# rf_swrmet6.net
KiCad netlist of a schematic drawn in Altium Designer
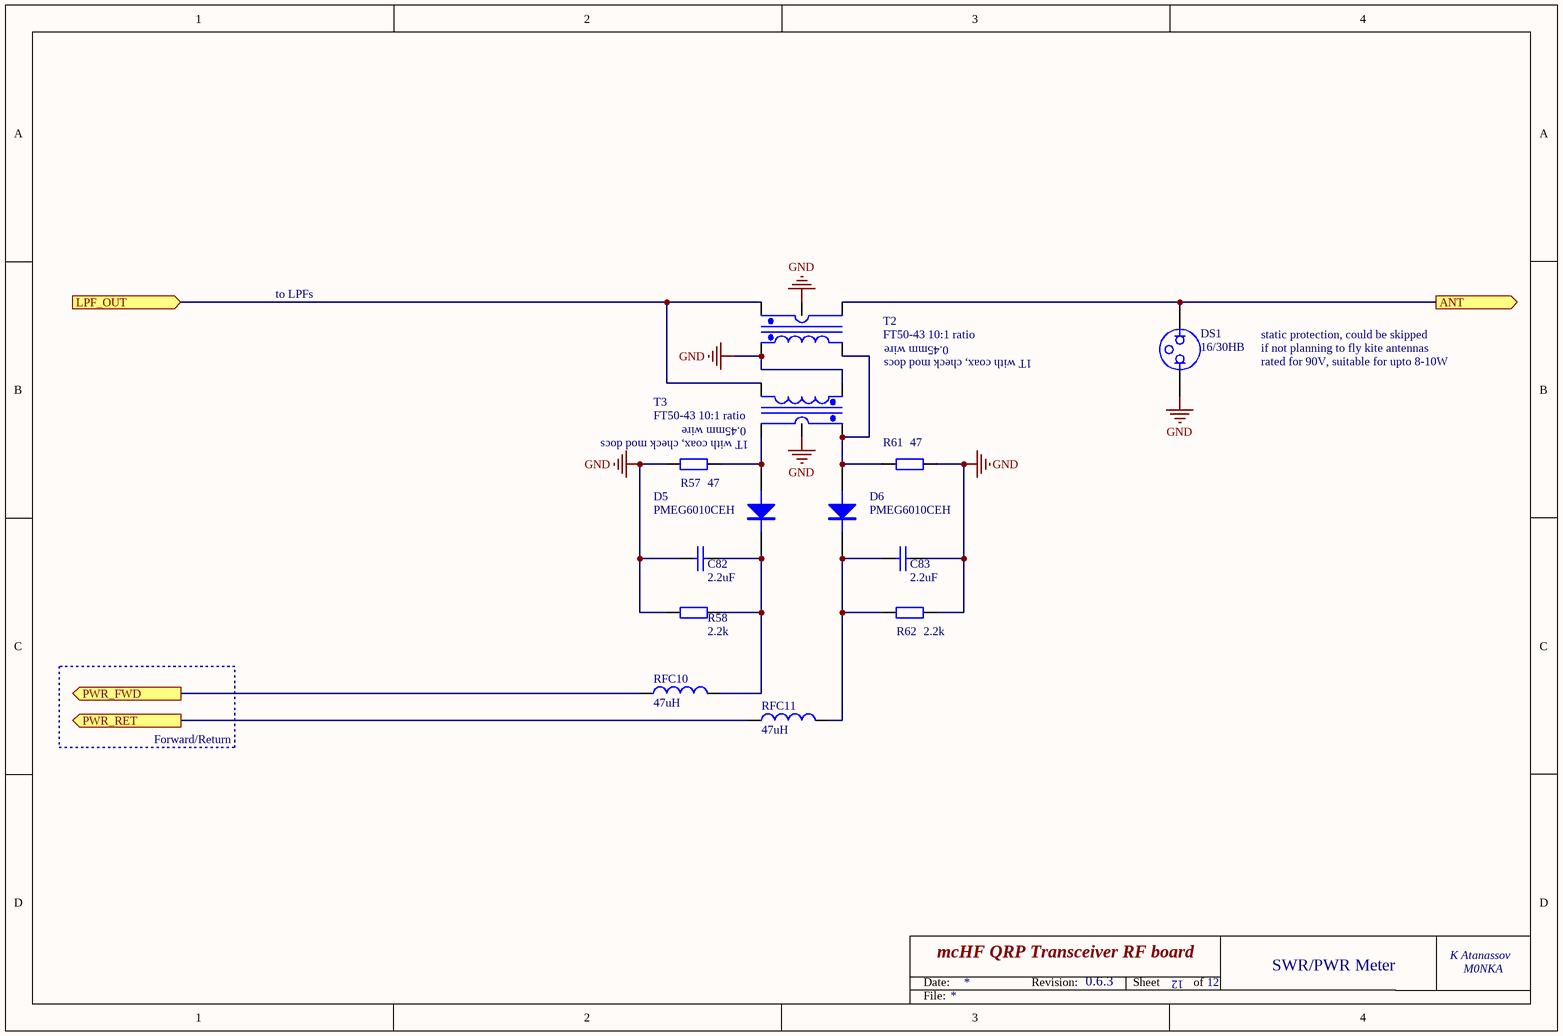
[diagram p0: rf_swrmet6.SchDoc]

(export (version "E")
  (design (tool "Eeschema 10.0.6"))
  (components
    (comp (ref "C82")
      (value "2.2uF")
      (footprint "0805-Pro")
      (description "Capacitor")
      (libsource (lib "mcHF_rf") (part "CAP"))
    )
    (comp (ref "C83")
      (value "2.2uF")
      (footprint "0805-Pro")
      (description "Capacitor")
      (libsource (lib "mcHF_rf") (part "CAP"))
    )
    (comp (ref "D5")
      (value "PMEG6010CEH")
      (footprint "SOD87")
      (description "DIODE, SCHOTTKY, 1A, 60V, SOD-123F")
      (libsource (lib "mcHF_rf") (part "PMEG6010CEH"))
    )
    (comp (ref "D6")
      (value "PMEG6010CEH")
      (footprint "SOD87")
      (description "DIODE, SCHOTTKY, 1A, 60V, SOD-123F")
      (libsource (lib "mcHF_rf") (part "PMEG6010CEH"))
    )
    (comp (ref "DS1")
      (value "16/30HB")
      (footprint "SIP2")
      (description "NEON LAMP, WIRE ENDED, T2")
      (libsource (lib "mcHF_rf") (part "16/30HB"))
    )
    (comp (ref "R57")
      (value "47")
      (footprint "0805-Pro")
      (description "Resistor")
      (libsource (lib "mcHF_rf") (part "RES"))
    )
    (comp (ref "R58")
      (value "2.2k")
      (footprint "0805-Pro")
      (description "Resistor")
      (libsource (lib "mcHF_rf") (part "RES"))
    )
    (comp (ref "R61")
      (value "47")
      (footprint "0805-Pro")
      (description "Resistor")
      (libsource (lib "mcHF_rf") (part "RES"))
    )
    (comp (ref "R62")
      (value "2.2k")
      (footprint "0805-Pro")
      (description "Resistor")
      (libsource (lib "mcHF_rf") (part "RES"))
    )
    (comp (ref "RFC10")
      (value "47uH")
      (footprint "0805-Pro")
      (description "INDUCTOR, SIGNAL LINE, 4.7UH, 1005")
      (libsource (lib "mcHF_rf") (part "TDK-NLV25T"))
    )
    (comp (ref "RFC11")
      (value "47uH")
      (footprint "0805-Pro")
      (description "INDUCTOR, SIGNAL LINE, 4.7UH, 1005")
      (libsource (lib "mcHF_rf") (part "TDK-NLV25T"))
    )
    (comp (ref "T2")
      (value "FT50-43 10:1 ratio")
      (footprint "SWR_TR _new")
      (description "SWR Bridge transformer")
      (libsource (lib "mcHF_rf") (part "SWR_TR"))
    )
    (comp (ref "T3")
      (value "FT50-43 10:1 ratio")
      (footprint "SWR_TR _new")
      (description "SWR Bridge transformer")
      (libsource (lib "mcHF_rf") (part "SWR_TR"))
    )
  )
  (nets
    (net (code "1") (name "/ANT") (class "Default")
      (node (ref "DS1") (pin "2") (pinfunction "2_2") (pintype "passive"))
      (node (ref "T2") (pin "4") (pinfunction "Sec-_4") (pintype "passive"))
    )
    (net (code "2") (name "/LPF_OUT") (class "Default")
      (node (ref "T2") (pin "3") (pinfunction "Sec+_3") (pintype "passive"))
      (node (ref "T3") (pin "2") (pinfunction "Pri-_2") (pintype "passive"))
    )
    (net (code "3") (name "/PWR_FWD") (class "Default")
      (node (ref "RFC10") (pin "1") (pinfunction "1_1") (pintype "passive"))
    )
    (net (code "4") (name "/PWR_RET") (class "Default")
      (node (ref "RFC11") (pin "1") (pinfunction "1_1") (pintype "passive"))
    )
    (net (code "5") (name "GND") (class "Default")
      (node (ref "C82") (pin "1") (pinfunction "1_1") (pintype "passive"))
      (node (ref "C83") (pin "2") (pinfunction "2_2") (pintype "passive"))
      (node (ref "DS1") (pin "1") (pinfunction "1_1") (pintype "passive"))
      (node (ref "R57") (pin "1") (pinfunction "1_1") (pintype "passive"))
      (node (ref "R58") (pin "1") (pinfunction "1_1") (pintype "passive"))
      (node (ref "R61") (pin "2") (pinfunction "2_2") (pintype "passive"))
      (node (ref "R62") (pin "2") (pinfunction "2_2") (pintype "passive"))
      (node (ref "T2") (pin "1") (pinfunction "Pri+_1") (pintype "passive"))
      (node (ref "T2") (pin "5") (pinfunction "Shield_5") (pintype "passive"))
      (node (ref "T3") (pin "1") (pinfunction "Pri+_1") (pintype "passive"))
      (node (ref "T3") (pin "5") (pinfunction "Shield_5") (pintype "passive"))
    )
    (net (code "6") (name "Net-(D5-A)") (class "Default")
      (node (ref "D5") (pin "1") (pinfunction "A_1") (pintype "passive"))
      (node (ref "R57") (pin "2") (pinfunction "2_2") (pintype "passive"))
      (node (ref "T3") (pin "4") (pinfunction "Sec-_4") (pintype "passive"))
    )
    (net (code "7") (name "Net-(D5-K)") (class "Default")
      (node (ref "C82") (pin "2") (pinfunction "2_2") (pintype "passive"))
      (node (ref "D5") (pin "2") (pinfunction "K_2") (pintype "passive"))
      (node (ref "R58") (pin "2") (pinfunction "2_2") (pintype "passive"))
      (node (ref "RFC10") (pin "2") (pinfunction "2_2") (pintype "passive"))
    )
    (net (code "8") (name "Net-(D6-A)") (class "Default")
      (node (ref "D6") (pin "1") (pinfunction "A_1") (pintype "passive"))
      (node (ref "R61") (pin "1") (pinfunction "1_1") (pintype "passive"))
      (node (ref "T2") (pin "2") (pinfunction "Pri-_2") (pintype "passive"))
      (node (ref "T3") (pin "3") (pinfunction "Sec+_3") (pintype "passive"))
    )
    (net (code "9") (name "Net-(D6-K)") (class "Default")
      (node (ref "C83") (pin "1") (pinfunction "1_1") (pintype "passive"))
      (node (ref "D6") (pin "2") (pinfunction "K_2") (pintype "passive"))
      (node (ref "R62") (pin "1") (pinfunction "1_1") (pintype "passive"))
      (node (ref "RFC11") (pin "2") (pinfunction "2_2") (pintype "passive"))
    )
  )
)
